# ampValve.net
KiCad netlist of a schematic drawn in EAGLE
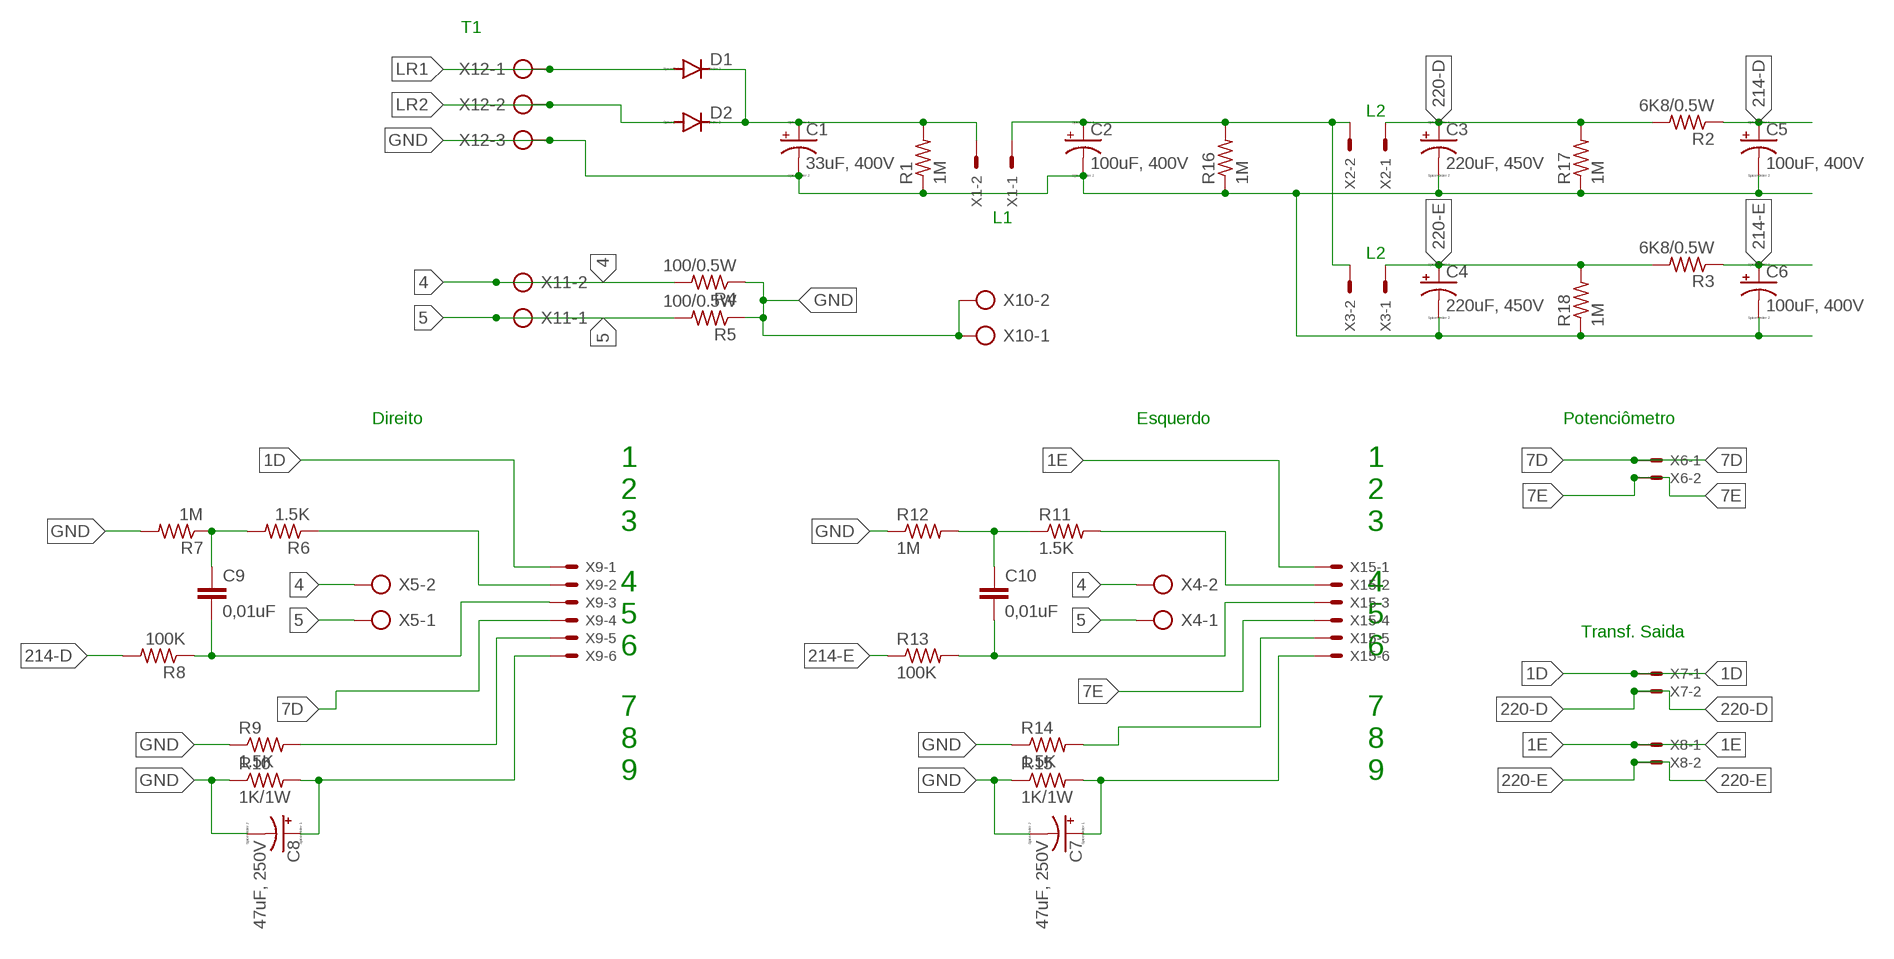
[diagram p0: schematic, sheet 1]

(export (version "E")
  (design (tool "Eeschema 10.0.6"))
  (components
    (comp (ref "C1")
      (value "33uF, 400V")
      (footprint "eagle-import:E7,5-16")
      (libsource (lib "eagle-import") (part "CPOL-USE7.5-16"))
    )
    (comp (ref "C2")
      (value "100uF, 400V")
      (footprint "eagle-import:E7,5-18")
      (libsource (lib "eagle-import") (part "CPOL-USE7.5-18"))
    )
    (comp (ref "C3")
      (value "220uF, 450V")
      (footprint "eagle-import:EB25D")
      (libsource (lib "eagle-import") (part "resistor_348_CPOL-USE10-25"))
    )
    (comp (ref "C4")
      (value "220uF, 450V")
      (footprint "eagle-import:EB25D")
      (libsource (lib "eagle-import") (part "resistor_348_CPOL-USE10-25"))
    )
    (comp (ref "C5")
      (value "100uF, 400V")
      (footprint "eagle-import:E7,5-18")
      (libsource (lib "eagle-import") (part "CPOL-USE7.5-18"))
    )
    (comp (ref "C6")
      (value "100uF, 400V")
      (footprint "eagle-import:E7,5-18")
      (libsource (lib "eagle-import") (part "CPOL-USE7.5-18"))
    )
    (comp (ref "C7")
      (value "47uF, 250V")
      (footprint "eagle-import:E5-13")
      (libsource (lib "eagle-import") (part "CPOL-USE5-13"))
    )
    (comp (ref "C8")
      (value "47uF, 250V")
      (footprint "eagle-import:E5-13")
      (libsource (lib "eagle-import") (part "CPOL-USE5-13"))
    )
    (comp (ref "C9")
      (value "0,01uF")
      (footprint "eagle-import:C102-043X133")
      (libsource (lib "eagle-import") (part "C-EU102-043X133"))
    )
    (comp (ref "C10")
      (value "0,01uF")
      (footprint "eagle-import:C102-043X133")
      (libsource (lib "eagle-import") (part "C-EU102-043X133"))
    )
    (comp (ref "D1")
      (value "DIODE-D-12.5")
      (footprint "eagle-import:D-12.5")
      (libsource (lib "eagle-import") (part "DIODE-D-12.5"))
    )
    (comp (ref "D2")
      (value "DIODE-D-12.5")
      (footprint "eagle-import:D-12.5")
      (libsource (lib "eagle-import") (part "DIODE-D-12.5"))
    )
    (comp (ref "R1")
      (value "1M")
      (footprint "eagle-import:0207_10")
      (libsource (lib "eagle-import") (part "R-US_0207/10"))
    )
    (comp (ref "R2")
      (value "6K8/0.5W")
      (footprint "eagle-import:0207_10")
      (libsource (lib "eagle-import") (part "R-US_0207/10"))
    )
    (comp (ref "R3")
      (value "6K8/0.5W")
      (footprint "eagle-import:0207_10")
      (libsource (lib "eagle-import") (part "R-US_0207/10"))
    )
    (comp (ref "R4")
      (value "100/0.5W")
      (footprint "eagle-import:0207_10")
      (libsource (lib "eagle-import") (part "R-US_0207/10"))
    )
    (comp (ref "R5")
      (value "100/0.5W")
      (footprint "eagle-import:0207_10")
      (libsource (lib "eagle-import") (part "R-US_0207/10"))
    )
    (comp (ref "R6")
      (value "1.5K")
      (footprint "eagle-import:0207_10")
      (libsource (lib "eagle-import") (part "R-US_0207/10"))
    )
    (comp (ref "R7")
      (value "1M")
      (footprint "eagle-import:0207_10")
      (libsource (lib "eagle-import") (part "R-US_0207/10"))
    )
    (comp (ref "R8")
      (value "100K")
      (footprint "eagle-import:0207_10")
      (libsource (lib "eagle-import") (part "R-US_0207/10"))
    )
    (comp (ref "R9")
      (value "1.5K")
      (footprint "eagle-import:0207_10")
      (libsource (lib "eagle-import") (part "R-US_0207/10"))
    )
    (comp (ref "R10")
      (value "1K/1W")
      (footprint "eagle-import:0207_10")
      (libsource (lib "eagle-import") (part "R-US_0207/10"))
    )
    (comp (ref "R11")
      (value "1.5K")
      (footprint "eagle-import:0207_10")
      (libsource (lib "eagle-import") (part "R-US_0207/10"))
    )
    (comp (ref "R12")
      (value "1M")
      (footprint "eagle-import:0207_10")
      (libsource (lib "eagle-import") (part "R-US_0207/10"))
    )
    (comp (ref "R13")
      (value "100K")
      (footprint "eagle-import:0207_10")
      (libsource (lib "eagle-import") (part "R-US_0207/10"))
    )
    (comp (ref "R14")
      (value "1.5K")
      (footprint "eagle-import:0207_10")
      (libsource (lib "eagle-import") (part "R-US_0207/10"))
    )
    (comp (ref "R15")
      (value "1K/1W")
      (footprint "eagle-import:0207_10")
      (libsource (lib "eagle-import") (part "R-US_0207/10"))
    )
    (comp (ref "R16")
      (value "1M")
      (footprint "eagle-import:0207_10")
      (libsource (lib "eagle-import") (part "R-US_0207/10"))
    )
    (comp (ref "R17")
      (value "1M")
      (footprint "eagle-import:0207_10")
      (libsource (lib "eagle-import") (part "R-US_0207/10"))
    )
    (comp (ref "R18")
      (value "1M")
      (footprint "eagle-import:0207_10")
      (libsource (lib "eagle-import") (part "R-US_0207/10"))
    )
    (comp (ref "X1")
      (value "KK-156-2")
      (footprint "eagle-import:KK-156-2")
      (fields (field (name "MF") "MOLEX"))
      (libsource (lib "eagle-import") (part "KK-156-2"))
    )
    (comp (ref "X2")
      (value "KK-156-2")
      (footprint "eagle-import:KK-156-2")
      (fields (field (name "MF") "MOLEX"))
      (libsource (lib "eagle-import") (part "KK-156-2"))
    )
    (comp (ref "X3")
      (value "KK-156-2")
      (footprint "eagle-import:KK-156-2")
      (fields (field (name "MF") "MOLEX"))
      (libsource (lib "eagle-import") (part "KK-156-2"))
    )
    (comp (ref "X4")
      (value "AK500/2-H")
      (footprint "eagle-import:AK500_2-H")
      (libsource (lib "eagle-import") (part "AK500/2-H"))
    )
    (comp (ref "X5")
      (value "AK500/2-H")
      (footprint "eagle-import:AK500_2-H")
      (libsource (lib "eagle-import") (part "AK500/2-H"))
    )
    (comp (ref "X6")
      (value "KK-156-2")
      (footprint "eagle-import:KK-156-2")
      (fields (field (name "MF") "MOLEX"))
      (libsource (lib "eagle-import") (part "KK-156-2"))
    )
    (comp (ref "X7")
      (value "KK-156-2")
      (footprint "eagle-import:KK-156-2")
      (fields (field (name "MF") "MOLEX"))
      (libsource (lib "eagle-import") (part "KK-156-2"))
    )
    (comp (ref "X8")
      (value "KK-156-2")
      (footprint "eagle-import:KK-156-2")
      (fields (field (name "MF") "MOLEX"))
      (libsource (lib "eagle-import") (part "KK-156-2"))
    )
    (comp (ref "X9")
      (value "KK-156-6")
      (footprint "eagle-import:KK-156-6")
      (fields (field (name "MF") "MOLEX"))
      (libsource (lib "eagle-import") (part "KK-156-6"))
    )
    (comp (ref "X10")
      (value "AK500/2-H")
      (footprint "eagle-import:AK500_2-H")
      (libsource (lib "eagle-import") (part "AK500/2-H"))
    )
    (comp (ref "X11")
      (value "AK500/2-H")
      (footprint "eagle-import:AK500_2-H")
      (libsource (lib "eagle-import") (part "AK500/2-H"))
    )
    (comp (ref "X12")
      (value "AK500/3-H")
      (footprint "eagle-import:AK500_3-H")
      (libsource (lib "eagle-import") (part "AK500/3-H"))
    )
    (comp (ref "X15")
      (value "KK-156-6")
      (footprint "eagle-import:KK-156-6")
      (fields (field (name "MF") "MOLEX"))
      (libsource (lib "eagle-import") (part "KK-156-6"))
    )
  )
  (nets
    (net (code "1") (name "1D") (class "Default")
      (node (ref "X7") (pin "1") (pinfunction "S_1") (pintype "passive"))
      (node (ref "X9") (pin "1") (pinfunction "S_1") (pintype "passive"))
    )
    (net (code "2") (name "1E") (class "Default")
      (node (ref "X15") (pin "1") (pinfunction "S_1") (pintype "passive"))
      (node (ref "X8") (pin "1") (pinfunction "S_1") (pintype "passive"))
    )
    (net (code "3") (name "4") (class "Default")
      (node (ref "R4") (pin "2") (pinfunction "2_2") (pintype "passive"))
      (node (ref "X11") (pin "2") (pinfunction "KL_2") (pintype "passive"))
      (node (ref "X4") (pin "2") (pinfunction "KL_2") (pintype "passive"))
      (node (ref "X5") (pin "2") (pinfunction "KL_2") (pintype "passive"))
    )
    (net (code "4") (name "5") (class "Default")
      (node (ref "R5") (pin "2") (pinfunction "2_2") (pintype "passive"))
      (node (ref "X11") (pin "1") (pinfunction "KL_1") (pintype "passive"))
      (node (ref "X4") (pin "1") (pinfunction "KL_1") (pintype "passive"))
      (node (ref "X5") (pin "1") (pinfunction "KL_1") (pintype "passive"))
    )
    (net (code "5") (name "7D") (class "Default")
      (node (ref "X6") (pin "1") (pinfunction "S_1") (pintype "passive"))
      (node (ref "X9") (pin "4") (pinfunction "S_4") (pintype "passive"))
    )
    (net (code "6") (name "7E") (class "Default")
      (node (ref "X15") (pin "4") (pinfunction "S_4") (pintype "passive"))
      (node (ref "X6") (pin "2") (pinfunction "S_2") (pintype "passive"))
    )
    (net (code "7") (name "214-D") (class "Default")
      (node (ref "C5") (pin "+") (pinfunction "+_+") (pintype "passive"))
      (node (ref "R2") (pin "1") (pinfunction "1_1") (pintype "passive"))
      (node (ref "R8") (pin "2") (pinfunction "2_2") (pintype "passive"))
    )
    (net (code "8") (name "214-E") (class "Default")
      (node (ref "C6") (pin "+") (pinfunction "+_+") (pintype "passive"))
      (node (ref "R13") (pin "1") (pinfunction "1_1") (pintype "passive"))
      (node (ref "R3") (pin "1") (pinfunction "1_1") (pintype "passive"))
    )
    (net (code "9") (name "220-D") (class "Default")
      (node (ref "C3") (pin "+") (pinfunction "+_+") (pintype "passive"))
      (node (ref "R17") (pin "2") (pinfunction "2_2") (pintype "passive"))
      (node (ref "R2") (pin "2") (pinfunction "2_2") (pintype "passive"))
      (node (ref "X2") (pin "1") (pinfunction "S_1") (pintype "passive"))
      (node (ref "X7") (pin "2") (pinfunction "S_2") (pintype "passive"))
    )
    (net (code "10") (name "220-E") (class "Default")
      (node (ref "C4") (pin "+") (pinfunction "+_+") (pintype "passive"))
      (node (ref "R18") (pin "2") (pinfunction "2_2") (pintype "passive"))
      (node (ref "R3") (pin "2") (pinfunction "2_2") (pintype "passive"))
      (node (ref "X3") (pin "1") (pinfunction "S_1") (pintype "passive"))
      (node (ref "X8") (pin "2") (pinfunction "S_2") (pintype "passive"))
    )
    (net (code "11") (name "GND") (class "Default")
      (node (ref "C1") (pin "-") (pinfunction "-_-") (pintype "passive"))
      (node (ref "C2") (pin "-") (pinfunction "-_-") (pintype "passive"))
      (node (ref "C3") (pin "-") (pinfunction "-_-") (pintype "passive"))
      (node (ref "C4") (pin "-") (pinfunction "-_-") (pintype "passive"))
      (node (ref "C5") (pin "-") (pinfunction "-_-") (pintype "passive"))
      (node (ref "C6") (pin "-") (pinfunction "-_-") (pintype "passive"))
      (node (ref "C7") (pin "-") (pinfunction "-_-") (pintype "passive"))
      (node (ref "C8") (pin "-") (pinfunction "-_-") (pintype "passive"))
      (node (ref "R1") (pin "1") (pinfunction "1_1") (pintype "passive"))
      (node (ref "R10") (pin "1") (pinfunction "1_1") (pintype "passive"))
      (node (ref "R12") (pin "1") (pinfunction "1_1") (pintype "passive"))
      (node (ref "R14") (pin "1") (pinfunction "1_1") (pintype "passive"))
      (node (ref "R15") (pin "1") (pinfunction "1_1") (pintype "passive"))
      (node (ref "R16") (pin "1") (pinfunction "1_1") (pintype "passive"))
      (node (ref "R17") (pin "1") (pinfunction "1_1") (pintype "passive"))
      (node (ref "R18") (pin "1") (pinfunction "1_1") (pintype "passive"))
      (node (ref "R4") (pin "1") (pinfunction "1_1") (pintype "passive"))
      (node (ref "R5") (pin "1") (pinfunction "1_1") (pintype "passive"))
      (node (ref "R7") (pin "2") (pinfunction "2_2") (pintype "passive"))
      (node (ref "R9") (pin "1") (pinfunction "1_1") (pintype "passive"))
      (node (ref "X10") (pin "1") (pinfunction "KL_1") (pintype "passive"))
      (node (ref "X10") (pin "2") (pinfunction "KL_2") (pintype "passive"))
      (node (ref "X12") (pin "3") (pinfunction "KL_3") (pintype "passive"))
    )
    (net (code "12") (name "LR1") (class "Default")
      (node (ref "D1") (pin "A") (pinfunction "A_A") (pintype "passive"))
      (node (ref "X12") (pin "1") (pinfunction "KL_1") (pintype "passive"))
    )
    (net (code "13") (name "LR2") (class "Default")
      (node (ref "D2") (pin "A") (pinfunction "A_A") (pintype "passive"))
      (node (ref "X12") (pin "2") (pinfunction "KL_2") (pintype "passive"))
    )
    (net (code "14") (name "Net-(C9-Pad1)") (class "Default")
      (node (ref "C9") (pin "1") (pinfunction "1_1") (pintype "passive"))
      (node (ref "R6") (pin "2") (pinfunction "2_2") (pintype "passive"))
      (node (ref "R7") (pin "1") (pinfunction "1_1") (pintype "passive"))
    )
    (net (code "15") (name "Net-(C10-Pad1)") (class "Default")
      (node (ref "C10") (pin "1") (pinfunction "1_1") (pintype "passive"))
      (node (ref "R11") (pin "1") (pinfunction "1_1") (pintype "passive"))
      (node (ref "R12") (pin "2") (pinfunction "2_2") (pintype "passive"))
    )
    (net (code "16") (name "Net-(X1A-S)") (class "Default")
      (node (ref "C2") (pin "+") (pinfunction "+_+") (pintype "passive"))
      (node (ref "R16") (pin "2") (pinfunction "2_2") (pintype "passive"))
      (node (ref "X1") (pin "1") (pinfunction "S_1") (pintype "passive"))
      (node (ref "X2") (pin "2") (pinfunction "S_2") (pintype "passive"))
      (node (ref "X3") (pin "2") (pinfunction "S_2") (pintype "passive"))
    )
    (net (code "17") (name "Net-(X1B-S)") (class "Default")
      (node (ref "C1") (pin "+") (pinfunction "+_+") (pintype "passive"))
      (node (ref "D1") (pin "C") (pinfunction "C_C") (pintype "passive"))
      (node (ref "D2") (pin "C") (pinfunction "C_C") (pintype "passive"))
      (node (ref "R1") (pin "2") (pinfunction "2_2") (pintype "passive"))
      (node (ref "X1") (pin "2") (pinfunction "S_2") (pintype "passive"))
    )
    (net (code "18") (name "Net-(X9B-S)") (class "Default")
      (node (ref "R6") (pin "1") (pinfunction "1_1") (pintype "passive"))
      (node (ref "X9") (pin "2") (pinfunction "S_2") (pintype "passive"))
    )
    (net (code "19") (name "Net-(X9C-S)") (class "Default")
      (node (ref "C9") (pin "2") (pinfunction "2_2") (pintype "passive"))
      (node (ref "R8") (pin "1") (pinfunction "1_1") (pintype "passive"))
      (node (ref "X9") (pin "3") (pinfunction "S_3") (pintype "passive"))
    )
    (net (code "20") (name "Net-(X9E-S)") (class "Default")
      (node (ref "R9") (pin "2") (pinfunction "2_2") (pintype "passive"))
      (node (ref "X9") (pin "5") (pinfunction "S_5") (pintype "passive"))
    )
    (net (code "21") (name "Net-(X9F-S)") (class "Default")
      (node (ref "C8") (pin "+") (pinfunction "+_+") (pintype "passive"))
      (node (ref "R10") (pin "2") (pinfunction "2_2") (pintype "passive"))
      (node (ref "X9") (pin "6") (pinfunction "S_6") (pintype "passive"))
    )
    (net (code "22") (name "Net-(X15B-S)") (class "Default")
      (node (ref "R11") (pin "2") (pinfunction "2_2") (pintype "passive"))
      (node (ref "X15") (pin "2") (pinfunction "S_2") (pintype "passive"))
    )
    (net (code "23") (name "Net-(X15C-S)") (class "Default")
      (node (ref "C10") (pin "2") (pinfunction "2_2") (pintype "passive"))
      (node (ref "R13") (pin "2") (pinfunction "2_2") (pintype "passive"))
      (node (ref "X15") (pin "3") (pinfunction "S_3") (pintype "passive"))
    )
    (net (code "24") (name "Net-(X15E-S)") (class "Default")
      (node (ref "R14") (pin "2") (pinfunction "2_2") (pintype "passive"))
      (node (ref "X15") (pin "5") (pinfunction "S_5") (pintype "passive"))
    )
    (net (code "25") (name "Net-(X15F-S)") (class "Default")
      (node (ref "C7") (pin "+") (pinfunction "+_+") (pintype "passive"))
      (node (ref "R15") (pin "2") (pinfunction "2_2") (pintype "passive"))
      (node (ref "X15") (pin "6") (pinfunction "S_6") (pintype "passive"))
    )
  )
)
